# PicoZed.net
KiCad netlist of a schematic drawn in Altium Designer
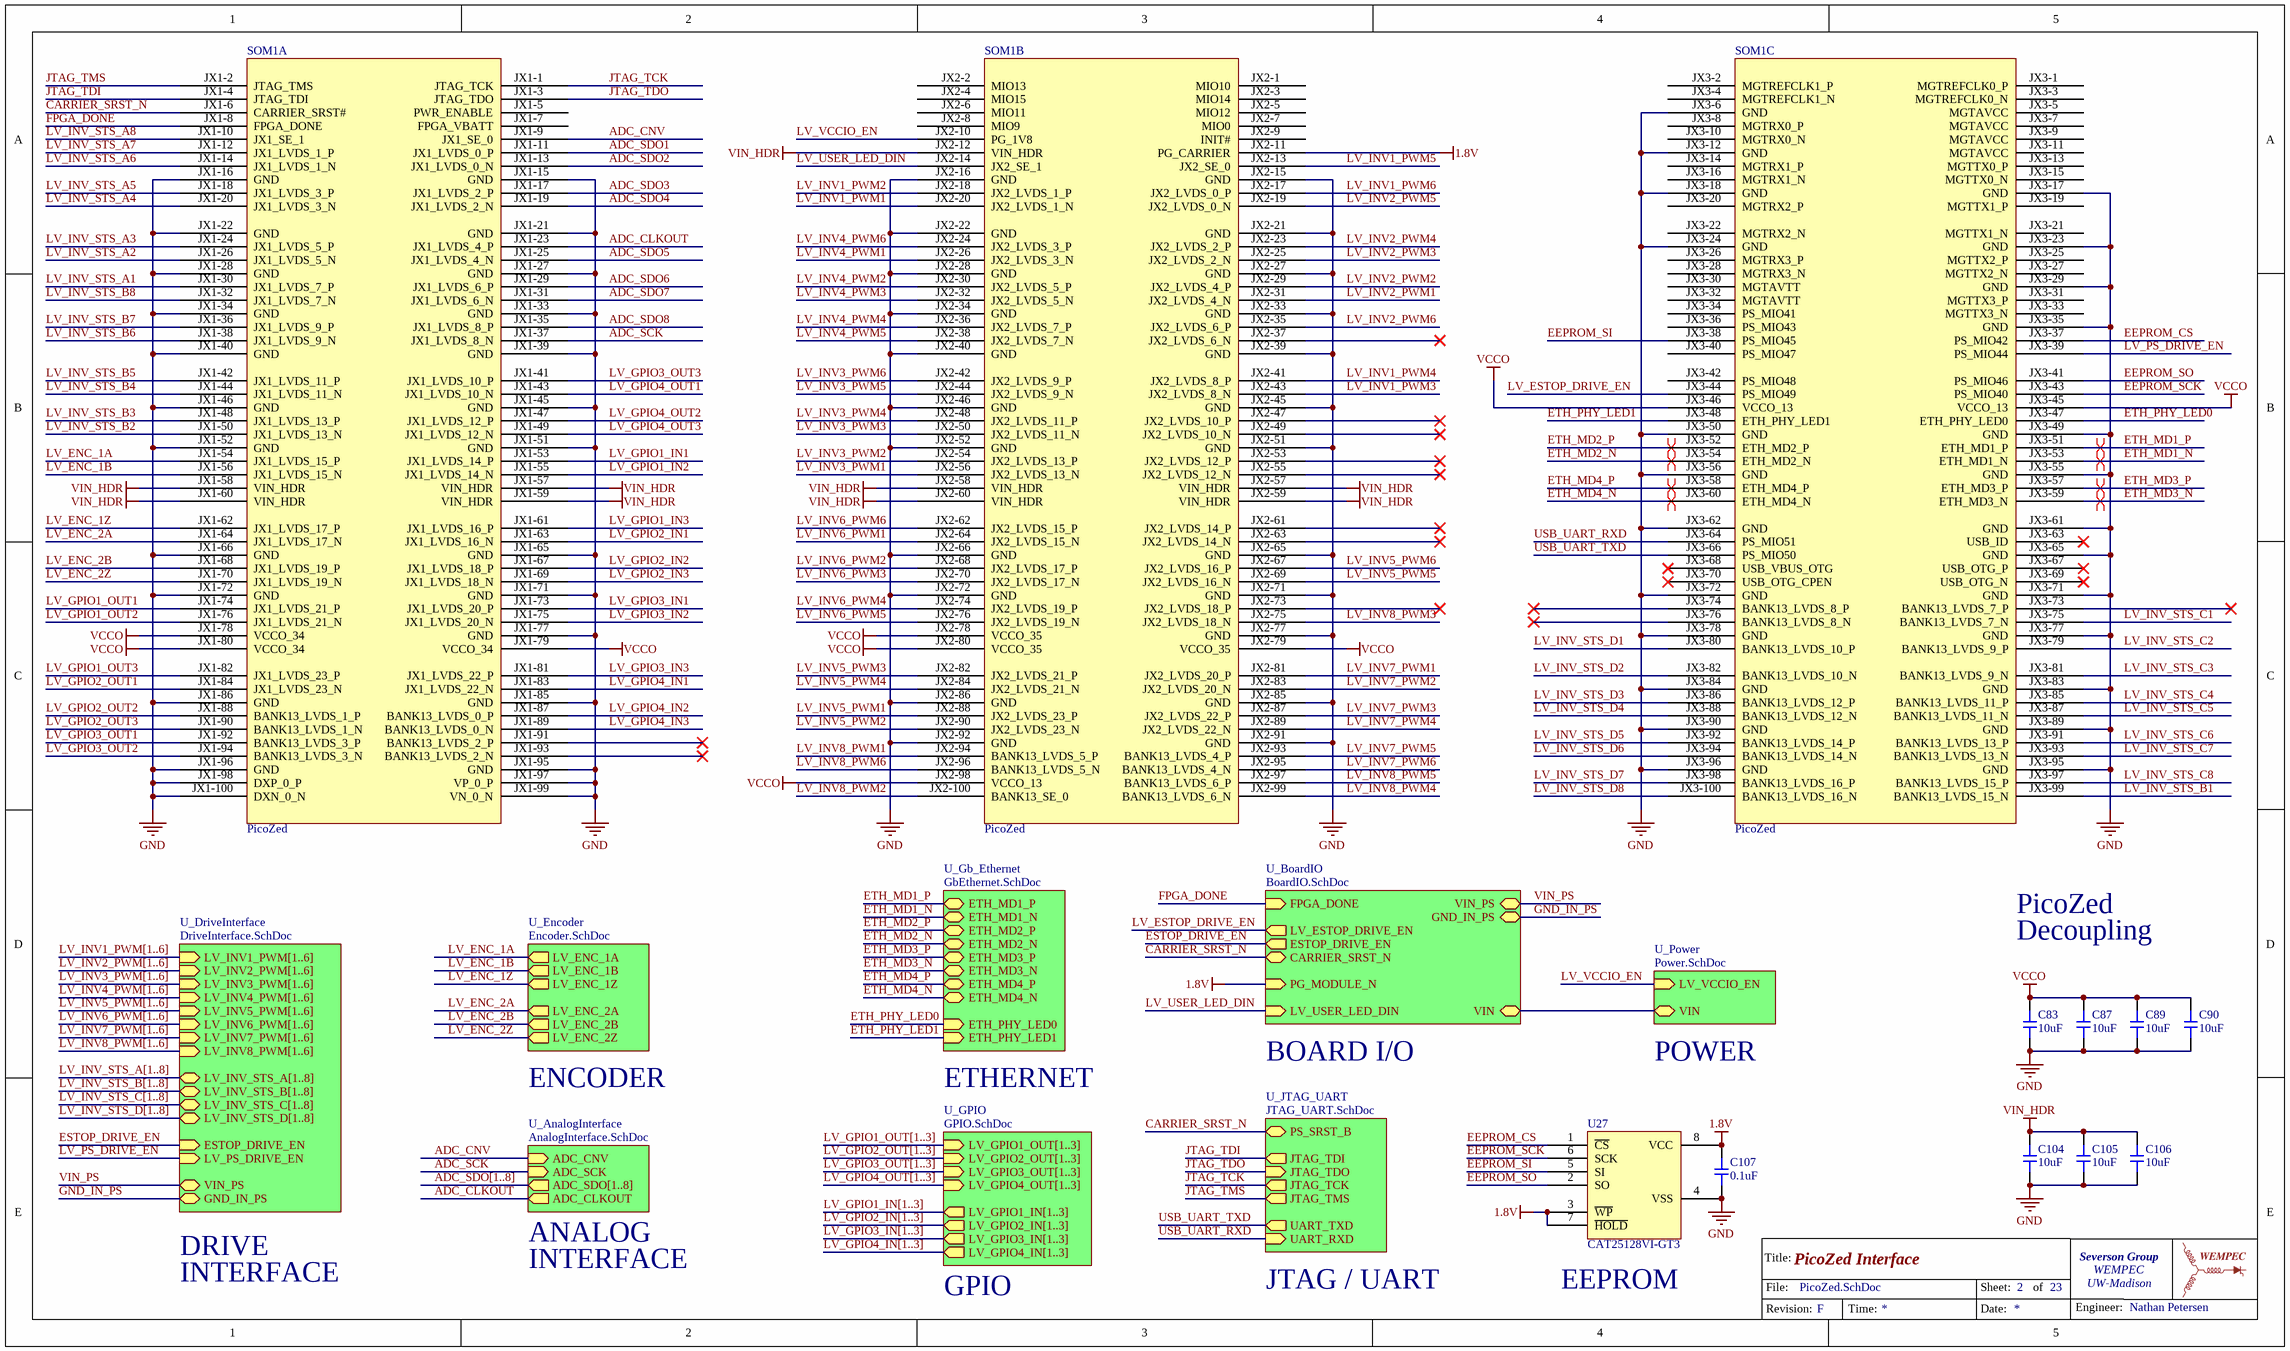
[diagram p0: PicoZed.SchDoc]

(export (version "E")
  (design (tool "Eeschema 10.0.6"))
  (components
    (comp (ref "*") (value "TitleBlockWEMPEC") (libsource (lib "AMDC") (part "TitleBlockWEMPEC")))
    (comp (ref "C83")
      (value "10uF")
      (footprint "0603-CAP")
      (description "Capacitor")
      (libsource (lib "AMDC") (part "Capacitor"))
    )
    (comp (ref "C87")
      (value "10uF")
      (footprint "0603-CAP")
      (description "Capacitor")
      (libsource (lib "AMDC") (part "Capacitor"))
    )
    (comp (ref "C89")
      (value "10uF")
      (footprint "0603-CAP")
      (description "Capacitor")
      (libsource (lib "AMDC") (part "Capacitor"))
    )
    (comp (ref "C90")
      (value "10uF")
      (footprint "0603-CAP")
      (description "Capacitor")
      (libsource (lib "AMDC") (part "Capacitor"))
    )
    (comp (ref "C104")
      (value "10uF")
      (footprint "0603-CAP")
      (description "Capacitor")
      (libsource (lib "AMDC") (part "Capacitor"))
    )
    (comp (ref "C105")
      (value "10uF")
      (footprint "0603-CAP")
      (description "Capacitor")
      (libsource (lib "AMDC") (part "Capacitor"))
    )
    (comp (ref "C106")
      (value "10uF")
      (footprint "0603-CAP")
      (description "Capacitor")
      (libsource (lib "AMDC") (part "Capacitor"))
    )
    (comp (ref "C107")
      (value "0.1uF")
      (footprint "0603-CAP")
      (description "Capacitor")
      (libsource (lib "AMDC") (part "Capacitor"))
    )
    (comp (ref "SOM1")
      (value "PicoZed")
      (footprint "PicoZedSOM")
      (description "PicoZed SOM Carrier Footprint")
      (libsource (lib "PicoZedSchLib") (part "PicoZed_SOM"))
    )
    (comp (ref "U27")
      (value "CAT25128VI-GT3")
      (footprint "SOIC127P600X175-8N")
      (description "IC EEPROM 128K SPI 20MHZ 8SOIC")
      (libsource (lib "AMDC") (part "CAT25128VI-GT3"))
    )
  )
  (nets
    (net (code "1") (name "/ADC_CLKOUT") (class "Default")
      (node (ref "SOM1") (pin "JX1-23") (pinfunction "JX1_LVDS_4_P_JX1-23") (pintype "passive"))
    )
    (net (code "2") (name "/ADC_CNV") (class "Default")
      (node (ref "SOM1") (pin "JX1-9") (pinfunction "JX1_SE_0_JX1-9") (pintype "passive"))
    )
    (net (code "3") (name "/ADC_SCK") (class "Default")
      (node (ref "SOM1") (pin "JX1-37") (pinfunction "JX1_LVDS_8_N_JX1-37") (pintype "passive"))
    )
    (net (code "4") (name "/ADC_SDO1") (class "Default")
      (node (ref "SOM1") (pin "JX1-11") (pinfunction "JX1_LVDS_0_P_JX1-11") (pintype "passive"))
    )
    (net (code "5") (name "/ADC_SDO2") (class "Default")
      (node (ref "SOM1") (pin "JX1-13") (pinfunction "JX1_LVDS_0_N_JX1-13") (pintype "passive"))
    )
    (net (code "6") (name "/ADC_SDO3") (class "Default")
      (node (ref "SOM1") (pin "JX1-17") (pinfunction "JX1_LVDS_2_P_JX1-17") (pintype "passive"))
    )
    (net (code "7") (name "/ADC_SDO4") (class "Default")
      (node (ref "SOM1") (pin "JX1-19") (pinfunction "JX1_LVDS_2_N_JX1-19") (pintype "passive"))
    )
    (net (code "8") (name "/ADC_SDO5") (class "Default")
      (node (ref "SOM1") (pin "JX1-25") (pinfunction "JX1_LVDS_4_N_JX1-25") (pintype "passive"))
    )
    (net (code "9") (name "/ADC_SDO6") (class "Default")
      (node (ref "SOM1") (pin "JX1-29") (pinfunction "JX1_LVDS_6_P_JX1-29") (pintype "passive"))
    )
    (net (code "10") (name "/ADC_SDO7") (class "Default")
      (node (ref "SOM1") (pin "JX1-31") (pinfunction "JX1_LVDS_6_N_JX1-31") (pintype "passive"))
    )
    (net (code "11") (name "/ADC_SDO8") (class "Default")
      (node (ref "SOM1") (pin "JX1-35") (pinfunction "JX1_LVDS_8_P_JX1-35") (pintype "passive"))
    )
    (net (code "13") (name "/CARRIER_SRST_N") (class "Default")
      (node (ref "SOM1") (pin "JX1-6") (pinfunction "CARRIER_SRST#_JX1-6") (pintype "passive"))
    )
    (net (code "14") (name "/EEPROM_CS") (class "Default")
      (node (ref "SOM1") (pin "JX3-37") (pinfunction "PS_MIO42_JX3-37") (pintype "passive"))
      (node (ref "U27") (pin "1") (pinfunction "~{CS}_1") (pintype "passive"))
    )
    (net (code "15") (name "/EEPROM_SCK") (class "Default")
      (node (ref "SOM1") (pin "JX3-43") (pinfunction "PS_MIO40_JX3-43") (pintype "passive"))
      (node (ref "U27") (pin "6") (pinfunction "SCK_6") (pintype "passive"))
    )
    (net (code "16") (name "/EEPROM_SI") (class "Default")
      (node (ref "SOM1") (pin "JX3-38") (pinfunction "PS_MIO45_JX3-38") (pintype "passive"))
      (node (ref "U27") (pin "5") (pinfunction "SI_5") (pintype "passive"))
    )
    (net (code "17") (name "/EEPROM_SO") (class "Default")
      (node (ref "SOM1") (pin "JX3-41") (pinfunction "PS_MIO46_JX3-41") (pintype "passive"))
      (node (ref "U27") (pin "2") (pinfunction "SO_2") (pintype "passive"))
    )
    (net (code "19") (name "/ETH_MD1_N") (class "Default")
      (node (ref "SOM1") (pin "JX3-53") (pinfunction "ETH_MD1_N_JX3-53") (pintype "passive"))
    )
    (net (code "20") (name "/ETH_MD1_P") (class "Default")
      (node (ref "SOM1") (pin "JX3-51") (pinfunction "ETH_MD1_P_JX3-51") (pintype "passive"))
    )
    (net (code "21") (name "/ETH_MD2_N") (class "Default")
      (node (ref "SOM1") (pin "JX3-54") (pinfunction "ETH_MD2_N_JX3-54") (pintype "passive"))
    )
    (net (code "22") (name "/ETH_MD2_P") (class "Default")
      (node (ref "SOM1") (pin "JX3-52") (pinfunction "ETH_MD2_P_JX3-52") (pintype "passive"))
    )
    (net (code "23") (name "/ETH_MD3_N") (class "Default")
      (node (ref "SOM1") (pin "JX3-59") (pinfunction "ETH_MD3_N_JX3-59") (pintype "passive"))
    )
    (net (code "24") (name "/ETH_MD3_P") (class "Default")
      (node (ref "SOM1") (pin "JX3-57") (pinfunction "ETH_MD3_P_JX3-57") (pintype "passive"))
    )
    (net (code "25") (name "/ETH_MD4_N") (class "Default")
      (node (ref "SOM1") (pin "JX3-60") (pinfunction "ETH_MD4_N_JX3-60") (pintype "passive"))
    )
    (net (code "26") (name "/ETH_MD4_P") (class "Default")
      (node (ref "SOM1") (pin "JX3-58") (pinfunction "ETH_MD4_P_JX3-58") (pintype "passive"))
    )
    (net (code "27") (name "/ETH_PHY_LED0") (class "Default")
      (node (ref "SOM1") (pin "JX3-47") (pinfunction "ETH_PHY_LED0_JX3-47") (pintype "passive"))
    )
    (net (code "28") (name "/ETH_PHY_LED1") (class "Default")
      (node (ref "SOM1") (pin "JX3-48") (pinfunction "ETH_PHY_LED1_JX3-48") (pintype "passive"))
    )
    (net (code "29") (name "/FPGA_DONE") (class "Default")
      (node (ref "SOM1") (pin "JX1-8") (pinfunction "FPGA_DONE_JX1-8") (pintype "passive"))
    )
    (net (code "31") (name "/JTAG_TCK") (class "Default")
      (node (ref "SOM1") (pin "JX1-1") (pinfunction "JTAG_TCK_JX1-1") (pintype "passive"))
    )
    (net (code "32") (name "/JTAG_TDI") (class "Default")
      (node (ref "SOM1") (pin "JX1-4") (pinfunction "JTAG_TDI_JX1-4") (pintype "passive"))
    )
    (net (code "33") (name "/JTAG_TDO") (class "Default")
      (node (ref "SOM1") (pin "JX1-3") (pinfunction "JTAG_TDO_JX1-3") (pintype "passive"))
    )
    (net (code "34") (name "/JTAG_TMS") (class "Default")
      (node (ref "SOM1") (pin "JX1-2") (pinfunction "JTAG_TMS_JX1-2") (pintype "passive"))
    )
    (net (code "35") (name "/LV_ENC_1A") (class "Default")
      (node (ref "SOM1") (pin "JX1-54") (pinfunction "JX1_LVDS_15_P_JX1-54") (pintype "passive"))
    )
    (net (code "36") (name "/LV_ENC_1B") (class "Default")
      (node (ref "SOM1") (pin "JX1-56") (pinfunction "JX1_LVDS_15_N_JX1-56") (pintype "passive"))
    )
    (net (code "37") (name "/LV_ENC_1Z") (class "Default")
      (node (ref "SOM1") (pin "JX1-62") (pinfunction "JX1_LVDS_17_P_JX1-62") (pintype "passive"))
    )
    (net (code "38") (name "/LV_ENC_2A") (class "Default")
      (node (ref "SOM1") (pin "JX1-64") (pinfunction "JX1_LVDS_17_N_JX1-64") (pintype "passive"))
    )
    (net (code "39") (name "/LV_ENC_2B") (class "Default")
      (node (ref "SOM1") (pin "JX1-68") (pinfunction "JX1_LVDS_19_P_JX1-68") (pintype "passive"))
    )
    (net (code "40") (name "/LV_ENC_2Z") (class "Default")
      (node (ref "SOM1") (pin "JX1-70") (pinfunction "JX1_LVDS_19_N_JX1-70") (pintype "passive"))
    )
    (net (code "41") (name "/LV_ESTOP_DRIVE_EN") (class "Default")
      (node (ref "SOM1") (pin "JX3-44") (pinfunction "PS_MIO49_JX3-44") (pintype "passive"))
    )
    (net (code "42") (name "/LV_GPIO1_IN1") (class "Default")
      (node (ref "SOM1") (pin "JX1-53") (pinfunction "JX1_LVDS_14_P_JX1-53") (pintype "passive"))
    )
    (net (code "43") (name "/LV_GPIO1_IN2") (class "Default")
      (node (ref "SOM1") (pin "JX1-55") (pinfunction "JX1_LVDS_14_N_JX1-55") (pintype "passive"))
    )
    (net (code "44") (name "/LV_GPIO1_IN3") (class "Default")
      (node (ref "SOM1") (pin "JX1-61") (pinfunction "JX1_LVDS_16_P_JX1-61") (pintype "passive"))
    )
    (net (code "46") (name "/LV_GPIO1_OUT1") (class "Default")
      (node (ref "SOM1") (pin "JX1-74") (pinfunction "JX1_LVDS_21_P_JX1-74") (pintype "passive"))
    )
    (net (code "47") (name "/LV_GPIO1_OUT2") (class "Default")
      (node (ref "SOM1") (pin "JX1-76") (pinfunction "JX1_LVDS_21_N_JX1-76") (pintype "passive"))
    )
    (net (code "48") (name "/LV_GPIO1_OUT3") (class "Default")
      (node (ref "SOM1") (pin "JX1-82") (pinfunction "JX1_LVDS_23_P_JX1-82") (pintype "passive"))
    )
    (net (code "50") (name "/LV_GPIO2_IN1") (class "Default")
      (node (ref "SOM1") (pin "JX1-63") (pinfunction "JX1_LVDS_16_N_JX1-63") (pintype "passive"))
    )
    (net (code "51") (name "/LV_GPIO2_IN2") (class "Default")
      (node (ref "SOM1") (pin "JX1-67") (pinfunction "JX1_LVDS_18_P_JX1-67") (pintype "passive"))
    )
    (net (code "52") (name "/LV_GPIO2_IN3") (class "Default")
      (node (ref "SOM1") (pin "JX1-69") (pinfunction "JX1_LVDS_18_N_JX1-69") (pintype "passive"))
    )
    (net (code "54") (name "/LV_GPIO2_OUT1") (class "Default")
      (node (ref "SOM1") (pin "JX1-84") (pinfunction "JX1_LVDS_23_N_JX1-84") (pintype "passive"))
    )
    (net (code "55") (name "/LV_GPIO2_OUT2") (class "Default")
      (node (ref "SOM1") (pin "JX1-88") (pinfunction "BANK13_LVDS_1_P_JX1-88") (pintype "passive"))
    )
    (net (code "56") (name "/LV_GPIO2_OUT3") (class "Default")
      (node (ref "SOM1") (pin "JX1-90") (pinfunction "BANK13_LVDS_1_N_JX1-90") (pintype "passive"))
    )
    (net (code "58") (name "/LV_GPIO3_IN1") (class "Default")
      (node (ref "SOM1") (pin "JX1-73") (pinfunction "JX1_LVDS_20_P_JX1-73") (pintype "passive"))
    )
    (net (code "59") (name "/LV_GPIO3_IN2") (class "Default")
      (node (ref "SOM1") (pin "JX1-75") (pinfunction "JX1_LVDS_20_N_JX1-75") (pintype "passive"))
    )
    (net (code "60") (name "/LV_GPIO3_IN3") (class "Default")
      (node (ref "SOM1") (pin "JX1-81") (pinfunction "JX1_LVDS_22_P_JX1-81") (pintype "passive"))
    )
    (net (code "62") (name "/LV_GPIO3_OUT1") (class "Default")
      (node (ref "SOM1") (pin "JX1-92") (pinfunction "BANK13_LVDS_3_P_JX1-92") (pintype "passive"))
    )
    (net (code "63") (name "/LV_GPIO3_OUT2") (class "Default")
      (node (ref "SOM1") (pin "JX1-94") (pinfunction "BANK13_LVDS_3_N_JX1-94") (pintype "passive"))
    )
    (net (code "64") (name "/LV_GPIO3_OUT3") (class "Default")
      (node (ref "SOM1") (pin "JX1-41") (pinfunction "JX1_LVDS_10_P_JX1-41") (pintype "passive"))
    )
    (net (code "66") (name "/LV_GPIO4_IN1") (class "Default")
      (node (ref "SOM1") (pin "JX1-83") (pinfunction "JX1_LVDS_22_N_JX1-83") (pintype "passive"))
    )
    (net (code "67") (name "/LV_GPIO4_IN2") (class "Default")
      (node (ref "SOM1") (pin "JX1-87") (pinfunction "BANK13_LVDS_0_P_JX1-87") (pintype "passive"))
    )
    (net (code "68") (name "/LV_GPIO4_IN3") (class "Default")
      (node (ref "SOM1") (pin "JX1-89") (pinfunction "BANK13_LVDS_0_N_JX1-89") (pintype "passive"))
    )
    (net (code "70") (name "/LV_GPIO4_OUT1") (class "Default")
      (node (ref "SOM1") (pin "JX1-43") (pinfunction "JX1_LVDS_10_N_JX1-43") (pintype "passive"))
    )
    (net (code "71") (name "/LV_GPIO4_OUT2") (class "Default")
      (node (ref "SOM1") (pin "JX1-47") (pinfunction "JX1_LVDS_12_P_JX1-47") (pintype "passive"))
    )
    (net (code "72") (name "/LV_GPIO4_OUT3") (class "Default")
      (node (ref "SOM1") (pin "JX1-49") (pinfunction "JX1_LVDS_12_N_JX1-49") (pintype "passive"))
    )
    (net (code "74") (name "/LV_INV1_PWM1") (class "Default")
      (node (ref "SOM1") (pin "JX2-20") (pinfunction "JX2_LVDS_1_N_JX2-20") (pintype "passive"))
    )
    (net (code "75") (name "/LV_INV1_PWM2") (class "Default")
      (node (ref "SOM1") (pin "JX2-18") (pinfunction "JX2_LVDS_1_P_JX2-18") (pintype "passive"))
    )
    (net (code "76") (name "/LV_INV1_PWM3") (class "Default")
      (node (ref "SOM1") (pin "JX2-43") (pinfunction "JX2_LVDS_8_N_JX2-43") (pintype "passive"))
    )
    (net (code "77") (name "/LV_INV1_PWM4") (class "Default")
      (node (ref "SOM1") (pin "JX2-41") (pinfunction "JX2_LVDS_8_P_JX2-41") (pintype "passive"))
    )
    (net (code "78") (name "/LV_INV1_PWM5") (class "Default")
      (node (ref "SOM1") (pin "JX2-13") (pinfunction "JX2_SE_0_JX2-13") (pintype "passive"))
    )
    (net (code "79") (name "/LV_INV1_PWM6") (class "Default")
      (node (ref "SOM1") (pin "JX2-17") (pinfunction "JX2_LVDS_0_P_JX2-17") (pintype "passive"))
    )
    (net (code "81") (name "/LV_INV2_PWM1") (class "Default")
      (node (ref "SOM1") (pin "JX2-31") (pinfunction "JX2_LVDS_4_N_JX2-31") (pintype "passive"))
    )
    (net (code "82") (name "/LV_INV2_PWM2") (class "Default")
      (node (ref "SOM1") (pin "JX2-29") (pinfunction "JX2_LVDS_4_P_JX2-29") (pintype "passive"))
    )
    (net (code "83") (name "/LV_INV2_PWM3") (class "Default")
      (node (ref "SOM1") (pin "JX2-25") (pinfunction "JX2_LVDS_2_N_JX2-25") (pintype "passive"))
    )
    (net (code "84") (name "/LV_INV2_PWM4") (class "Default")
      (node (ref "SOM1") (pin "JX2-23") (pinfunction "JX2_LVDS_2_P_JX2-23") (pintype "passive"))
    )
    (net (code "85") (name "/LV_INV2_PWM5") (class "Default")
      (node (ref "SOM1") (pin "JX2-19") (pinfunction "JX2_LVDS_0_N_JX2-19") (pintype "passive"))
    )
    (net (code "86") (name "/LV_INV2_PWM6") (class "Default")
      (node (ref "SOM1") (pin "JX2-35") (pinfunction "JX2_LVDS_6_P_JX2-35") (pintype "passive"))
    )
    (net (code "88") (name "/LV_INV3_PWM1") (class "Default")
      (node (ref "SOM1") (pin "JX2-56") (pinfunction "JX2_LVDS_13_N_JX2-56") (pintype "passive"))
    )
    (net (code "89") (name "/LV_INV3_PWM2") (class "Default")
      (node (ref "SOM1") (pin "JX2-54") (pinfunction "JX2_LVDS_13_P_JX2-54") (pintype "passive"))
    )
    (net (code "90") (name "/LV_INV3_PWM3") (class "Default")
      (node (ref "SOM1") (pin "JX2-50") (pinfunction "JX2_LVDS_11_N_JX2-50") (pintype "passive"))
    )
    (net (code "91") (name "/LV_INV3_PWM4") (class "Default")
      (node (ref "SOM1") (pin "JX2-48") (pinfunction "JX2_LVDS_11_P_JX2-48") (pintype "passive"))
    )
    (net (code "92") (name "/LV_INV3_PWM5") (class "Default")
      (node (ref "SOM1") (pin "JX2-44") (pinfunction "JX2_LVDS_9_N_JX2-44") (pintype "passive"))
    )
    (net (code "93") (name "/LV_INV3_PWM6") (class "Default")
      (node (ref "SOM1") (pin "JX2-42") (pinfunction "JX2_LVDS_9_P_JX2-42") (pintype "passive"))
    )
    (net (code "95") (name "/LV_INV4_PWM1") (class "Default")
      (node (ref "SOM1") (pin "JX2-26") (pinfunction "JX2_LVDS_3_N_JX2-26") (pintype "passive"))
    )
    (net (code "96") (name "/LV_INV4_PWM2") (class "Default")
      (node (ref "SOM1") (pin "JX2-30") (pinfunction "JX2_LVDS_5_P_JX2-30") (pintype "passive"))
    )
    (net (code "97") (name "/LV_INV4_PWM3") (class "Default")
      (node (ref "SOM1") (pin "JX2-32") (pinfunction "JX2_LVDS_5_N_JX2-32") (pintype "passive"))
    )
    (net (code "98") (name "/LV_INV4_PWM4") (class "Default")
      (node (ref "SOM1") (pin "JX2-36") (pinfunction "JX2_LVDS_7_P_JX2-36") (pintype "passive"))
    )
    (net (code "99") (name "/LV_INV4_PWM5") (class "Default")
      (node (ref "SOM1") (pin "JX2-38") (pinfunction "JX2_LVDS_7_N_JX2-38") (pintype "passive"))
    )
    (net (code "100") (name "/LV_INV4_PWM6") (class "Default")
      (node (ref "SOM1") (pin "JX2-24") (pinfunction "JX2_LVDS_3_P_JX2-24") (pintype "passive"))
    )
    (net (code "102") (name "/LV_INV5_PWM1") (class "Default")
      (node (ref "SOM1") (pin "JX2-88") (pinfunction "JX2_LVDS_23_P_JX2-88") (pintype "passive"))
    )
    (net (code "103") (name "/LV_INV5_PWM2") (class "Default")
      (node (ref "SOM1") (pin "JX2-90") (pinfunction "JX2_LVDS_23_N_JX2-90") (pintype "passive"))
    )
    (net (code "104") (name "/LV_INV5_PWM3") (class "Default")
      (node (ref "SOM1") (pin "JX2-82") (pinfunction "JX2_LVDS_21_P_JX2-82") (pintype "passive"))
    )
    (net (code "105") (name "/LV_INV5_PWM4") (class "Default")
      (node (ref "SOM1") (pin "JX2-84") (pinfunction "JX2_LVDS_21_N_JX2-84") (pintype "passive"))
    )
    (net (code "106") (name "/LV_INV5_PWM5") (class "Default")
      (node (ref "SOM1") (pin "JX2-69") (pinfunction "JX2_LVDS_16_N_JX2-69") (pintype "passive"))
    )
    (net (code "107") (name "/LV_INV5_PWM6") (class "Default")
      (node (ref "SOM1") (pin "JX2-67") (pinfunction "JX2_LVDS_16_P_JX2-67") (pintype "passive"))
    )
    (net (code "109") (name "/LV_INV6_PWM1") (class "Default")
      (node (ref "SOM1") (pin "JX2-64") (pinfunction "JX2_LVDS_15_N_JX2-64") (pintype "passive"))
    )
    (net (code "110") (name "/LV_INV6_PWM2") (class "Default")
      (node (ref "SOM1") (pin "JX2-68") (pinfunction "JX2_LVDS_17_P_JX2-68") (pintype "passive"))
    )
    (net (code "111") (name "/LV_INV6_PWM3") (class "Default")
      (node (ref "SOM1") (pin "JX2-70") (pinfunction "JX2_LVDS_17_N_JX2-70") (pintype "passive"))
    )
    (net (code "112") (name "/LV_INV6_PWM4") (class "Default")
      (node (ref "SOM1") (pin "JX2-74") (pinfunction "JX2_LVDS_19_P_JX2-74") (pintype "passive"))
    )
    (net (code "113") (name "/LV_INV6_PWM5") (class "Default")
      (node (ref "SOM1") (pin "JX2-76") (pinfunction "JX2_LVDS_19_N_JX2-76") (pintype "passive"))
    )
    (net (code "114") (name "/LV_INV6_PWM6") (class "Default")
      (node (ref "SOM1") (pin "JX2-62") (pinfunction "JX2_LVDS_15_P_JX2-62") (pintype "passive"))
    )
    (net (code "116") (name "/LV_INV7_PWM1") (class "Default")
      (node (ref "SOM1") (pin "JX2-81") (pinfunction "JX2_LVDS_20_P_JX2-81") (pintype "passive"))
    )
    (net (code "117") (name "/LV_INV7_PWM2") (class "Default")
      (node (ref "SOM1") (pin "JX2-83") (pinfunction "JX2_LVDS_20_N_JX2-83") (pintype "passive"))
    )
    (net (code "118") (name "/LV_INV7_PWM3") (class "Default")
      (node (ref "SOM1") (pin "JX2-87") (pinfunction "JX2_LVDS_22_P_JX2-87") (pintype "passive"))
    )
    (net (code "119") (name "/LV_INV7_PWM4") (class "Default")
      (node (ref "SOM1") (pin "JX2-89") (pinfunction "JX2_LVDS_22_N_JX2-89") (pintype "passive"))
    )
    (net (code "120") (name "/LV_INV7_PWM5") (class "Default")
      (node (ref "SOM1") (pin "JX2-93") (pinfunction "BANK13_LVDS_4_P_JX2-93") (pintype "passive"))
    )
    (net (code "121") (name "/LV_INV7_PWM6") (class "Default")
      (node (ref "SOM1") (pin "JX2-95") (pinfunction "BANK13_LVDS_4_N_JX2-95") (pintype "passive"))
    )
    (net (code "123") (name "/LV_INV8_PWM1") (class "Default")
      (node (ref "SOM1") (pin "JX2-94") (pinfunction "BANK13_LVDS_5_P_JX2-94") (pintype "passive"))
    )
    (net (code "124") (name "/LV_INV8_PWM2") (class "Default")
      (node (ref "SOM1") (pin "JX2-100") (pinfunction "BANK13_SE_0_JX2-100") (pintype "passive"))
    )
    (net (code "125") (name "/LV_INV8_PWM3") (class "Default")
      (node (ref "SOM1") (pin "JX2-75") (pinfunction "JX2_LVDS_18_N_JX2-75") (pintype "passive"))
    )
    (net (code "126") (name "/LV_INV8_PWM4") (class "Default")
      (node (ref "SOM1") (pin "JX2-99") (pinfunction "BANK13_LVDS_6_N_JX2-99") (pintype "passive"))
    )
    (net (code "127") (name "/LV_INV8_PWM5") (class "Default")
      (node (ref "SOM1") (pin "JX2-97") (pinfunction "BANK13_LVDS_6_P_JX2-97") (pintype "passive"))
    )
    (net (code "128") (name "/LV_INV8_PWM6") (class "Default")
      (node (ref "SOM1") (pin "JX2-96") (pinfunction "BANK13_LVDS_5_N_JX2-96") (pintype "passive"))
    )
    (net (code "130") (name "/LV_INV_STS_A1") (class "Default")
      (node (ref "SOM1") (pin "JX1-30") (pinfunction "JX1_LVDS_7_P_JX1-30") (pintype "passive"))
    )
    (net (code "131") (name "/LV_INV_STS_A2") (class "Default")
      (node (ref "SOM1") (pin "JX1-26") (pinfunction "JX1_LVDS_5_N_JX1-26") (pintype "passive"))
    )
    (net (code "132") (name "/LV_INV_STS_A3") (class "Default")
      (node (ref "SOM1") (pin "JX1-24") (pinfunction "JX1_LVDS_5_P_JX1-24") (pintype "passive"))
    )
    (net (code "133") (name "/LV_INV_STS_A4") (class "Default")
      (node (ref "SOM1") (pin "JX1-20") (pinfunction "JX1_LVDS_3_N_JX1-20") (pintype "passive"))
    )
    (net (code "134") (name "/LV_INV_STS_A5") (class "Default")
      (node (ref "SOM1") (pin "JX1-18") (pinfunction "JX1_LVDS_3_P_JX1-18") (pintype "passive"))
    )
    (net (code "135") (name "/LV_INV_STS_A6") (class "Default")
      (node (ref "SOM1") (pin "JX1-14") (pinfunction "JX1_LVDS_1_N_JX1-14") (pintype "passive"))
    )
    (net (code "136") (name "/LV_INV_STS_A7") (class "Default")
      (node (ref "SOM1") (pin "JX1-12") (pinfunction "JX1_LVDS_1_P_JX1-12") (pintype "passive"))
    )
    (net (code "137") (name "/LV_INV_STS_A8") (class "Default")
      (node (ref "SOM1") (pin "JX1-10") (pinfunction "JX1_SE_1_JX1-10") (pintype "passive"))
    )
    (net (code "139") (name "/LV_INV_STS_B1") (class "Default")
      (node (ref "SOM1") (pin "JX3-99") (pinfunction "BANK13_LVDS_15_N_JX3-99") (pintype "passive"))
    )
    (net (code "140") (name "/LV_INV_STS_B2") (class "Default")
      (node (ref "SOM1") (pin "JX1-50") (pinfunction "JX1_LVDS_13_N_JX1-50") (pintype "passive"))
    )
    (net (code "141") (name "/LV_INV_STS_B3") (class "Default")
      (node (ref "SOM1") (pin "JX1-48") (pinfunction "JX1_LVDS_13_P_JX1-48") (pintype "passive"))
    )
    (net (code "142") (name "/LV_INV_STS_B4") (class "Default")
      (node (ref "SOM1") (pin "JX1-44") (pinfunction "JX1_LVDS_11_N_JX1-44") (pintype "passive"))
    )
    (net (code "143") (name "/LV_INV_STS_B5") (class "Default")
      (node (ref "SOM1") (pin "JX1-42") (pinfunction "JX1_LVDS_11_P_JX1-42") (pintype "passive"))
    )
    (net (code "144") (name "/LV_INV_STS_B6") (class "Default")
      (node (ref "SOM1") (pin "JX1-38") (pinfunction "JX1_LVDS_9_N_JX1-38") (pintype "passive"))
    )
    (net (code "145") (name "/LV_INV_STS_B7") (class "Default")
      (node (ref "SOM1") (pin "JX1-36") (pinfunction "JX1_LVDS_9_P_JX1-36") (pintype "passive"))
    )
    (net (code "146") (name "/LV_INV_STS_B8") (class "Default")
      (node (ref "SOM1") (pin "JX1-32") (pinfunction "JX1_LVDS_7_N_JX1-32") (pintype "passive"))
    )
    (net (code "148") (name "/LV_INV_STS_C1") (class "Default")
      (node (ref "SOM1") (pin "JX3-75") (pinfunction "BANK13_LVDS_7_N_JX3-75") (pintype "passive"))
    )
    (net (code "149") (name "/LV_INV_STS_C2") (class "Default")
      (node (ref "SOM1") (pin "JX3-79") (pinfunction "BANK13_LVDS_9_P_JX3-79") (pintype "passive"))
    )
    (net (code "150") (name "/LV_INV_STS_C3") (class "Default")
      (node (ref "SOM1") (pin "JX3-81") (pinfunction "BANK13_LVDS_9_N_JX3-81") (pintype "passive"))
    )
    (net (code "151") (name "/LV_INV_STS_C4") (class "Default")
      (node (ref "SOM1") (pin "JX3-85") (pinfunction "BANK13_LVDS_11_P_JX3-85") (pintype "passive"))
    )
    (net (code "152") (name "/LV_INV_STS_C5") (class "Default")
      (node (ref "SOM1") (pin "JX3-87") (pinfunction "BANK13_LVDS_11_N_JX3-87") (pintype "passive"))
    )
    (net (code "153") (name "/LV_INV_STS_C6") (class "Default")
      (node (ref "SOM1") (pin "JX3-91") (pinfunction "BANK13_LVDS_13_P_JX3-91") (pintype "passive"))
    )
    (net (code "154") (name "/LV_INV_STS_C7") (class "Default")
      (node (ref "SOM1") (pin "JX3-93") (pinfunction "BANK13_LVDS_13_N_JX3-93") (pintype "passive"))
    )
    (net (code "155") (name "/LV_INV_STS_C8") (class "Default")
      (node (ref "SOM1") (pin "JX3-97") (pinfunction "BANK13_LVDS_15_P_JX3-97") (pintype "passive"))
    )
    (net (code "157") (name "/LV_INV_STS_D1") (class "Default")
      (node (ref "SOM1") (pin "JX3-80") (pinfunction "BANK13_LVDS_10_P_JX3-80") (pintype "passive"))
    )
    (net (code "158") (name "/LV_INV_STS_D2") (class "Default")
      (node (ref "SOM1") (pin "JX3-82") (pinfunction "BANK13_LVDS_10_N_JX3-82") (pintype "passive"))
    )
    (net (code "159") (name "/LV_INV_STS_D3") (class "Default")
      (node (ref "SOM1") (pin "JX3-86") (pinfunction "BANK13_LVDS_12_P_JX3-86") (pintype "passive"))
    )
    (net (code "160") (name "/LV_INV_STS_D4") (class "Default")
      (node (ref "SOM1") (pin "JX3-88") (pinfunction "BANK13_LVDS_12_N_JX3-88") (pintype "passive"))
    )
    (net (code "161") (name "/LV_INV_STS_D5") (class "Default")
      (node (ref "SOM1") (pin "JX3-92") (pinfunction "BANK13_LVDS_14_P_JX3-92") (pintype "passive"))
    )
    (net (code "162") (name "/LV_INV_STS_D6") (class "Default")
      (node (ref "SOM1") (pin "JX3-94") (pinfunction "BANK13_LVDS_14_N_JX3-94") (pintype "passive"))
    )
    (net (code "163") (name "/LV_INV_STS_D7") (class "Default")
      (node (ref "SOM1") (pin "JX3-98") (pinfunction "BANK13_LVDS_16_P_JX3-98") (pintype "passive"))
    )
    (net (code "164") (name "/LV_INV_STS_D8") (class "Default")
      (node (ref "SOM1") (pin "JX3-100") (pinfunction "BANK13_LVDS_16_N_JX3-100") (pintype "passive"))
    )
    (net (code "166") (name "/LV_PS_DRIVE_EN") (class "Default")
      (node (ref "SOM1") (pin "JX3-39") (pinfunction "PS_MIO44_JX3-39") (pintype "passive"))
    )
    (net (code "167") (name "/LV_USER_LED_DIN") (class "Default")
      (node (ref "SOM1") (pin "JX2-14") (pinfunction "JX2_SE_1_JX2-14") (pintype "passive"))
    )
    (net (code "168") (name "/LV_VCCIO_EN") (class "Default")
      (node (ref "SOM1") (pin "JX2-10") (pinfunction "PG_1V8_JX2-10") (pintype "passive"))
    )
    (net (code "169") (name "/USB_UART_RXD") (class "Default")
      (node (ref "SOM1") (pin "JX3-64") (pinfunction "PS_MIO51_JX3-64") (pintype "passive"))
    )
    (net (code "170") (name "/USB_UART_TXD") (class "Default")
      (node (ref "SOM1") (pin "JX3-66") (pinfunction "PS_MIO50_JX3-66") (pintype "passive"))
    )
    (net (code "173") (name "1.8V") (class "Default")
      (node (ref "C107") (pin "2") (pinfunction "2_2") (pintype "passive"))
      (node (ref "SOM1") (pin "JX2-11") (pinfunction "PG_CARRIER_JX2-11") (pintype "passive"))
      (node (ref "U27") (pin "3") (pinfunction "~{WP}_3") (pintype "passive"))
      (node (ref "U27") (pin "7") (pinfunction "~{HOLD}_7") (pintype "passive"))
      (node (ref "U27") (pin "8") (pinfunction "VCC_8") (pintype "passive"))
    )
    (net (code "174") (name "GND") (class "Default")
      (node (ref "C104") (pin "1") (pinfunction "1_1") (pintype "passive"))
      (node (ref "C105") (pin "1") (pinfunction "1_1") (pintype "passive"))
      (node (ref "C106") (pin "1") (pinfunction "1_1") (pintype "passive"))
      (node (ref "C107") (pin "1") (pinfunction "1_1") (pintype "passive"))
      (node (ref "C83") (pin "1") (pinfunction "1_1") (pintype "passive"))
      (node (ref "C87") (pin "1") (pinfunction "1_1") (pintype "passive"))
      (node (ref "C89") (pin "1") (pinfunction "1_1") (pintype "passive"))
      (node (ref "C90") (pin "1") (pinfunction "1_1") (pintype "passive"))
      (node (ref "SOM1") (pin "JX1-100") (pinfunction "DXN_0_N_JX1-100") (pintype "passive"))
      (node (ref "SOM1") (pin "JX1-15") (pinfunction "GND_JX1-15") (pintype "passive"))
      (node (ref "SOM1") (pin "JX1-16") (pinfunction "GND_JX1-16") (pintype "passive"))
      (node (ref "SOM1") (pin "JX1-21") (pinfunction "GND_JX1-21") (pintype "passive"))
      (node (ref "SOM1") (pin "JX1-22") (pinfunction "GND_JX1-22") (pintype "passive"))
      (node (ref "SOM1") (pin "JX1-27") (pinfunction "GND_JX1-27") (pintype "passive"))
      (node (ref "SOM1") (pin "JX1-28") (pinfunction "GND_JX1-28") (pintype "passive"))
      (node (ref "SOM1") (pin "JX1-33") (pinfunction "GND_JX1-33") (pintype "passive"))
      (node (ref "SOM1") (pin "JX1-34") (pinfunction "GND_JX1-34") (pintype "passive"))
      (node (ref "SOM1") (pin "JX1-39") (pinfunction "GND_JX1-39") (pintype "passive"))
      (node (ref "SOM1") (pin "JX1-40") (pinfunction "GND_JX1-40") (pintype "passive"))
      (node (ref "SOM1") (pin "JX1-45") (pinfunction "GND_JX1-45") (pintype "passive"))
      (node (ref "SOM1") (pin "JX1-46") (pinfunction "GND_JX1-46") (pintype "passive"))
      (node (ref "SOM1") (pin "JX1-51") (pinfunction "GND_JX1-51") (pintype "passive"))
      (node (ref "SOM1") (pin "JX1-52") (pinfunction "GND_JX1-52") (pintype "passive"))
      (node (ref "SOM1") (pin "JX1-65") (pinfunction "GND_JX1-65") (pintype "passive"))
      (node (ref "SOM1") (pin "JX1-66") (pinfunction "GND_JX1-66") (pintype "passive"))
      (node (ref "SOM1") (pin "JX1-71") (pinfunction "GND_JX1-71") (pintype "passive"))
      (node (ref "SOM1") (pin "JX1-72") (pinfunction "GND_JX1-72") (pintype "passive"))
      (node (ref "SOM1") (pin "JX1-77") (pinfunction "GND_JX1-77") (pintype "passive"))
      (node (ref "SOM1") (pin "JX1-85") (pinfunction "GND_JX1-85") (pintype "passive"))
      (node (ref "SOM1") (pin "JX1-86") (pinfunction "GND_JX1-86") (pintype "passive"))
      (node (ref "SOM1") (pin "JX1-95") (pinfunction "GND_JX1-95") (pintype "passive"))
      (node (ref "SOM1") (pin "JX1-96") (pinfunction "GND_JX1-96") (pintype "passive"))
      (node (ref "SOM1") (pin "JX1-97") (pinfunction "VP_0_P_JX1-97") (pintype "passive"))
      (node (ref "SOM1") (pin "JX1-98") (pinfunction "DXP_0_P_JX1-98") (pintype "passive"))
      (node (ref "SOM1") (pin "JX1-99") (pinfunction "VN_0_N_JX1-99") (pintype "passive"))
      (node (ref "SOM1") (pin "JX2-15") (pinfunction "GND_JX2-15") (pintype "passive"))
      (node (ref "SOM1") (pin "JX2-16") (pinfunction "GND_JX2-16") (pintype "passive"))
      (node (ref "SOM1") (pin "JX2-21") (pinfunction "GND_JX2-21") (pintype "passive"))
      (node (ref "SOM1") (pin "JX2-22") (pinfunction "GND_JX2-22") (pintype "passive"))
      (node (ref "SOM1") (pin "JX2-27") (pinfunction "GND_JX2-27") (pintype "passive"))
      (node (ref "SOM1") (pin "JX2-28") (pinfunction "GND_JX2-28") (pintype "passive"))
      (node (ref "SOM1") (pin "JX2-33") (pinfunction "GND_JX2-33") (pintype "passive"))
      (node (ref "SOM1") (pin "JX2-34") (pinfunction "GND_JX2-34") (pintype "passive"))
      (node (ref "SOM1") (pin "JX2-39") (pinfunction "GND_JX2-39") (pintype "passive"))
      (node (ref "SOM1") (pin "JX2-40") (pinfunction "GND_JX2-40") (pintype "passive"))
      (node (ref "SOM1") (pin "JX2-45") (pinfunction "GND_JX2-45") (pintype "passive"))
      (node (ref "SOM1") (pin "JX2-46") (pinfunction "GND_JX2-46") (pintype "passive"))
      (node (ref "SOM1") (pin "JX2-51") (pinfunction "GND_JX2-51") (pintype "passive"))
      (node (ref "SOM1") (pin "JX2-52") (pinfunction "GND_JX2-52") (pintype "passive"))
      (node (ref "SOM1") (pin "JX2-65") (pinfunction "GND_JX2-65") (pintype "passive"))
      (node (ref "SOM1") (pin "JX2-66") (pinfunction "GND_JX2-66") (pintype "passive"))
      (node (ref "SOM1") (pin "JX2-71") (pinfunction "GND_JX2-71") (pintype "passive"))
      (node (ref "SOM1") (pin "JX2-72") (pinfunction "GND_JX2-72") (pintype "passive"))
      (node (ref "SOM1") (pin "JX2-77") (pinfunction "GND_JX2-77") (pintype "passive"))
      (node (ref "SOM1") (pin "JX2-85") (pinfunction "GND_JX2-85") (pintype "passive"))
      (node (ref "SOM1") (pin "JX2-86") (pinfunction "GND_JX2-86") (pintype "passive"))
      (node (ref "SOM1") (pin "JX2-91") (pinfunction "GND_JX2-91") (pintype "passive"))
      (node (ref "SOM1") (pin "JX2-92") (pinfunction "GND_JX2-92") (pintype "passive"))
      (node (ref "SOM1") (pin "JX3-12") (pinfunction "GND_JX3-12") (pintype "passive"))
      (node (ref "SOM1") (pin "JX3-17") (pinfunction "GND_JX3-17") (pintype "passive"))
      (node (ref "SOM1") (pin "JX3-18") (pinfunction "GND_JX3-18") (pintype "passive"))
      (node (ref "SOM1") (pin "JX3-23") (pinfunction "GND_JX3-23") (pintype "passive"))
      (node (ref "SOM1") (pin "JX3-24") (pinfunction "GND_JX3-24") (pintype "passive"))
      (node (ref "SOM1") (pin "JX3-29") (pinfunction "GND_JX3-29") (pintype "passive"))
      (node (ref "SOM1") (pin "JX3-35") (pinfunction "GND_JX3-35") (pintype "passive"))
      (node (ref "SOM1") (pin "JX3-49") (pinfunction "GND_JX3-49") (pintype "passive"))
      (node (ref "SOM1") (pin "JX3-50") (pinfunction "GND_JX3-50") (pintype "passive"))
      (node (ref "SOM1") (pin "JX3-55") (pinfunction "GND_JX3-55") (pintype "passive"))
      (node (ref "SOM1") (pin "JX3-56") (pinfunction "GND_JX3-56") (pintype "passive"))
      (node (ref "SOM1") (pin "JX3-6") (pinfunction "GND_JX3-6") (pintype "passive"))
      (node (ref "SOM1") (pin "JX3-61") (pinfunction "GND_JX3-61") (pintype "passive"))
      (node (ref "SOM1") (pin "JX3-62") (pinfunction "GND_JX3-62") (pintype "passive"))
      (node (ref "SOM1") (pin "JX3-65") (pinfunction "GND_JX3-65") (pintype "passive"))
      (node (ref "SOM1") (pin "JX3-71") (pinfunction "GND_JX3-71") (pintype "passive"))
      (node (ref "SOM1") (pin "JX3-72") (pinfunction "GND_JX3-72") (pintype "passive"))
      (node (ref "SOM1") (pin "JX3-77") (pinfunction "GND_JX3-77") (pintype "passive"))
      (node (ref "SOM1") (pin "JX3-78") (pinfunction "GND_JX3-78") (pintype "passive"))
      (node (ref "SOM1") (pin "JX3-83") (pinfunction "GND_JX3-83") (pintype "passive"))
      (node (ref "SOM1") (pin "JX3-84") (pinfunction "GND_JX3-84") (pintype "passive"))
      (node (ref "SOM1") (pin "JX3-89") (pinfunction "GND_JX3-89") (pintype "passive"))
      (node (ref "SOM1") (pin "JX3-90") (pinfunction "GND_JX3-90") (pintype "passive"))
      (node (ref "SOM1") (pin "JX3-95") (pinfunction "GND_JX3-95") (pintype "passive"))
      (node (ref "SOM1") (pin "JX3-96") (pinfunction "GND_JX3-96") (pintype "passive"))
      (node (ref "U27") (pin "4") (pinfunction "VSS_4") (pintype "passive"))
    )
    (net (code "175") (name "VCCO") (class "Default")
      (node (ref "C83") (pin "2") (pinfunction "2_2") (pintype "passive"))
      (node (ref "C87") (pin "2") (pinfunction "2_2") (pintype "passive"))
      (node (ref "C89") (pin "2") (pinfunction "2_2") (pintype "passive"))
      (node (ref "C90") (pin "2") (pinfunction "2_2") (pintype "passive"))
      (node (ref "SOM1") (pin "JX1-78") (pinfunction "VCCO_34_JX1-78") (pintype "passive"))
      (node (ref "SOM1") (pin "JX1-79") (pinfunction "VCCO_34_JX1-79") (pintype "passive"))
      (node (ref "SOM1") (pin "JX1-80") (pinfunction "VCCO_34_JX1-80") (pintype "passive"))
      (node (ref "SOM1") (pin "JX2-78") (pinfunction "VCCO_35_JX2-78") (pintype "passive"))
      (node (ref "SOM1") (pin "JX2-79") (pinfunction "VCCO_35_JX2-79") (pintype "passive"))
      (node (ref "SOM1") (pin "JX2-80") (pinfunction "VCCO_35_JX2-80") (pintype "passive"))
      (node (ref "SOM1") (pin "JX2-98") (pinfunction "VCCO_13_JX2-98") (pintype "passive"))
      (node (ref "SOM1") (pin "JX3-45") (pinfunction "VCCO_13_JX3-45") (pintype "passive"))
      (node (ref "SOM1") (pin "JX3-46") (pinfunction "VCCO_13_JX3-46") (pintype "passive"))
    )
    (net (code "176") (name "VIN_HDR") (class "Default")
      (node (ref "C104") (pin "2") (pinfunction "2_2") (pintype "passive"))
      (node (ref "C105") (pin "2") (pinfunction "2_2") (pintype "passive"))
      (node (ref "C106") (pin "2") (pinfunction "2_2") (pintype "passive"))
      (node (ref "SOM1") (pin "JX1-57") (pinfunction "VIN_HDR_JX1-57") (pintype "passive"))
      (node (ref "SOM1") (pin "JX1-58") (pinfunction "VIN_HDR_JX1-58") (pintype "passive"))
      (node (ref "SOM1") (pin "JX1-59") (pinfunction "VIN_HDR_JX1-59") (pintype "passive"))
      (node (ref "SOM1") (pin "JX1-60") (pinfunction "VIN_HDR_JX1-60") (pintype "passive"))
      (node (ref "SOM1") (pin "JX2-12") (pinfunction "VIN_HDR_JX2-12") (pintype "passive"))
      (node (ref "SOM1") (pin "JX2-57") (pinfunction "VIN_HDR_JX2-57") (pintype "passive"))
      (node (ref "SOM1") (pin "JX2-58") (pinfunction "VIN_HDR_JX2-58") (pintype "passive"))
      (node (ref "SOM1") (pin "JX2-59") (pinfunction "VIN_HDR_JX2-59") (pintype "passive"))
      (node (ref "SOM1") (pin "JX2-60") (pinfunction "VIN_HDR_JX2-60") (pintype "passive"))
    )
    (net (code "177") (name "unconnected-(SOM1A-BANK13_LVDS_2_N-PadJX1-93)") (class "Default")
      (node (ref "SOM1") (pin "JX1-93") (pinfunction "BANK13_LVDS_2_N_JX1-93") (pintype "passive+no_connect"))
    )
    (net (code "178") (name "unconnected-(SOM1A-BANK13_LVDS_2_P-PadJX1-91)") (class "Default")
      (node (ref "SOM1") (pin "JX1-91") (pinfunction "BANK13_LVDS_2_P_JX1-91") (pintype "passive+no_connect"))
    )
    (net (code "179") (name "unconnected-(SOM1A-FPGA_VBATT-PadJX1-7)") (class "Default")
      (node (ref "SOM1") (pin "JX1-7") (pinfunction "FPGA_VBATT_JX1-7") (pintype "passive"))
    )
    (net (code "180") (name "unconnected-(SOM1A-PWR_ENABLE-PadJX1-5)") (class "Default")
      (node (ref "SOM1") (pin "JX1-5") (pinfunction "PWR_ENABLE_JX1-5") (pintype "passive"))
    )
    (net (code "181") (name "unconnected-(SOM1B-INIT#-PadJX2-9)") (class "Default")
      (node (ref "SOM1") (pin "JX2-9") (pinfunction "INIT#_JX2-9") (pintype "passive"))
    )
    (net (code "182") (name "unconnected-(SOM1B-JX2_LVDS_6_N-PadJX2-37)") (class "Default")
      (node (ref "SOM1") (pin "JX2-37") (pinfunction "JX2_LVDS_6_N_JX2-37") (pintype "passive+no_connect"))
    )
    (net (code "183") (name "unconnected-(SOM1B-JX2_LVDS_10_N-PadJX2-49)") (class "Default")
      (node (ref "SOM1") (pin "JX2-49") (pinfunction "JX2_LVDS_10_N_JX2-49") (pintype "passive+no_connect"))
    )
    (net (code "184") (name "unconnected-(SOM1B-JX2_LVDS_10_P-PadJX2-47)") (class "Default")
      (node (ref "SOM1") (pin "JX2-47") (pinfunction "JX2_LVDS_10_P_JX2-47") (pintype "passive+no_connect"))
    )
    (net (code "185") (name "unconnected-(SOM1B-JX2_LVDS_12_N-PadJX2-55)") (class "Default")
      (node (ref "SOM1") (pin "JX2-55") (pinfunction "JX2_LVDS_12_N_JX2-55") (pintype "passive+no_connect"))
    )
    (net (code "186") (name "unconnected-(SOM1B-JX2_LVDS_12_P-PadJX2-53)") (class "Default")
      (node (ref "SOM1") (pin "JX2-53") (pinfunction "JX2_LVDS_12_P_JX2-53") (pintype "passive+no_connect"))
    )
    (net (code "187") (name "unconnected-(SOM1B-JX2_LVDS_14_N-PadJX2-63)") (class "Default")
      (node (ref "SOM1") (pin "JX2-63") (pinfunction "JX2_LVDS_14_N_JX2-63") (pintype "passive+no_connect"))
    )
    (net (code "188") (name "unconnected-(SOM1B-JX2_LVDS_14_P-PadJX2-61)") (class "Default")
      (node (ref "SOM1") (pin "JX2-61") (pinfunction "JX2_LVDS_14_P_JX2-61") (pintype "passive+no_connect"))
    )
    (net (code "189") (name "unconnected-(SOM1B-JX2_LVDS_18_P-PadJX2-73)") (class "Default")
      (node (ref "SOM1") (pin "JX2-73") (pinfunction "JX2_LVDS_18_P_JX2-73") (pintype "passive+no_connect"))
    )
    (net (code "190") (name "unconnected-(SOM1B-MIO0-PadJX2-7)") (class "Default")
      (node (ref "SOM1") (pin "JX2-7") (pinfunction "MIO0_JX2-7") (pintype "passive"))
    )
    (net (code "191") (name "unconnected-(SOM1B-MIO9-PadJX2-8)") (class "Default")
      (node (ref "SOM1") (pin "JX2-8") (pinfunction "MIO9_JX2-8") (pintype "passive"))
    )
    (net (code "192") (name "unconnected-(SOM1B-MIO10-PadJX2-1)") (class "Default")
      (node (ref "SOM1") (pin "JX2-1") (pinfunction "MIO10_JX2-1") (pintype "passive"))
    )
    (net (code "193") (name "unconnected-(SOM1B-MIO11-PadJX2-6)") (class "Default")
      (node (ref "SOM1") (pin "JX2-6") (pinfunction "MIO11_JX2-6") (pintype "passive"))
    )
    (net (code "194") (name "unconnected-(SOM1B-MIO12-PadJX2-5)") (class "Default")
      (node (ref "SOM1") (pin "JX2-5") (pinfunction "MIO12_JX2-5") (pintype "passive"))
    )
    (net (code "195") (name "unconnected-(SOM1B-MIO13-PadJX2-2)") (class "Default")
      (node (ref "SOM1") (pin "JX2-2") (pinfunction "MIO13_JX2-2") (pintype "passive"))
    )
    (net (code "196") (name "unconnected-(SOM1B-MIO14-PadJX2-3)") (class "Default")
      (node (ref "SOM1") (pin "JX2-3") (pinfunction "MIO14_JX2-3") (pintype "passive"))
    )
    (net (code "197") (name "unconnected-(SOM1B-MIO15-PadJX2-4)") (class "Default")
      (node (ref "SOM1") (pin "JX2-4") (pinfunction "MIO15_JX2-4") (pintype "passive"))
    )
    (net (code "198") (name "unconnected-(SOM1C-BANK13_LVDS_7_P-PadJX3-73)") (class "Default")
      (node (ref "SOM1") (pin "JX3-73") (pinfunction "BANK13_LVDS_7_P_JX3-73") (pintype "passive+no_connect"))
    )
    (net (code "199") (name "unconnected-(SOM1C-BANK13_LVDS_8_N-PadJX3-76)") (class "Default")
      (node (ref "SOM1") (pin "JX3-76") (pinfunction "BANK13_LVDS_8_N_JX3-76") (pintype "passive+no_connect"))
    )
    (net (code "200") (name "unconnected-(SOM1C-BANK13_LVDS_8_P-PadJX3-74)") (class "Default")
      (node (ref "SOM1") (pin "JX3-74") (pinfunction "BANK13_LVDS_8_P_JX3-74") (pintype "passive+no_connect"))
    )
    (net (code "201") (name "unconnected-(SOM1C-MGTAVCC-PadJX3-5)") (class "Default")
      (node (ref "SOM1") (pin "JX3-5") (pinfunction "MGTAVCC_JX3-5") (pintype "passive"))
    )
    (net (code "202") (name "unconnected-(SOM1C-MGTAVCC-PadJX3-7)") (class "Default")
      (node (ref "SOM1") (pin "JX3-7") (pinfunction "MGTAVCC_JX3-7") (pintype "passive"))
    )
    (net (code "203") (name "unconnected-(SOM1C-MGTAVCC-PadJX3-9)") (class "Default")
      (node (ref "SOM1") (pin "JX3-9") (pinfunction "MGTAVCC_JX3-9") (pintype "passive"))
    )
    (net (code "204") (name "unconnected-(SOM1C-MGTAVCC-PadJX3-11)") (class "Default")
      (node (ref "SOM1") (pin "JX3-11") (pinfunction "MGTAVCC_JX3-11") (pintype "passive"))
    )
    (net (code "205") (name "unconnected-(SOM1C-MGTAVTT-PadJX3-30)") (class "Default")
      (node (ref "SOM1") (pin "JX3-30") (pinfunction "MGTAVTT_JX3-30") (pintype "passive"))
    )
    (net (code "206") (name "unconnected-(SOM1C-MGTAVTT-PadJX3-32)") (class "Default")
      (node (ref "SOM1") (pin "JX3-32") (pinfunction "MGTAVTT_JX3-32") (pintype "passive"))
    )
    (net (code "207") (name "unconnected-(SOM1C-MGTREFCLK0_N-PadJX3-3)") (class "Default")
      (node (ref "SOM1") (pin "JX3-3") (pinfunction "MGTREFCLK0_N_JX3-3") (pintype "passive"))
    )
    (net (code "208") (name "unconnected-(SOM1C-MGTREFCLK0_P-PadJX3-1)") (class "Default")
      (node (ref "SOM1") (pin "JX3-1") (pinfunction "MGTREFCLK0_P_JX3-1") (pintype "passive"))
    )
    (net (code "209") (name "unconnected-(SOM1C-MGTREFCLK1_N-PadJX3-4)") (class "Default")
      (node (ref "SOM1") (pin "JX3-4") (pinfunction "MGTREFCLK1_N_JX3-4") (pintype "passive"))
    )
    (net (code "210") (name "unconnected-(SOM1C-MGTREFCLK1_P-PadJX3-2)") (class "Default")
      (node (ref "SOM1") (pin "JX3-2") (pinfunction "MGTREFCLK1_P_JX3-2") (pintype "passive"))
    )
    (net (code "211") (name "unconnected-(SOM1C-MGTRX0_N-PadJX3-10)") (class "Default")
      (node (ref "SOM1") (pin "JX3-10") (pinfunction "MGTRX0_N_JX3-10") (pintype "passive"))
    )
    (net (code "212") (name "unconnected-(SOM1C-MGTRX0_P-PadJX3-8)") (class "Default")
      (node (ref "SOM1") (pin "JX3-8") (pinfunction "MGTRX0_P_JX3-8") (pintype "passive"))
    )
    (net (code "213") (name "unconnected-(SOM1C-MGTRX1_N-PadJX3-16)") (class "Default")
      (node (ref "SOM1") (pin "JX3-16") (pinfunction "MGTRX1_N_JX3-16") (pintype "passive"))
    )
    (net (code "214") (name "unconnected-(SOM1C-MGTRX1_P-PadJX3-14)") (class "Default")
      (node (ref "SOM1") (pin "JX3-14") (pinfunction "MGTRX1_P_JX3-14") (pintype "passive"))
    )
    (net (code "215") (name "unconnected-(SOM1C-MGTRX2_N-PadJX3-22)") (class "Default")
      (node (ref "SOM1") (pin "JX3-22") (pinfunction "MGTRX2_N_JX3-22") (pintype "passive"))
    )
    (net (code "216") (name "unconnected-(SOM1C-MGTRX2_P-PadJX3-20)") (class "Default")
      (node (ref "SOM1") (pin "JX3-20") (pinfunction "MGTRX2_P_JX3-20") (pintype "passive"))
    )
    (net (code "217") (name "unconnected-(SOM1C-MGTRX3_N-PadJX3-28)") (class "Default")
      (node (ref "SOM1") (pin "JX3-28") (pinfunction "MGTRX3_N_JX3-28") (pintype "passive"))
    )
    (net (code "218") (name "unconnected-(SOM1C-MGTRX3_P-PadJX3-26)") (class "Default")
      (node (ref "SOM1") (pin "JX3-26") (pinfunction "MGTRX3_P_JX3-26") (pintype "passive"))
    )
    (net (code "219") (name "unconnected-(SOM1C-MGTTX0_N-PadJX3-15)") (class "Default")
      (node (ref "SOM1") (pin "JX3-15") (pinfunction "MGTTX0_N_JX3-15") (pintype "passive"))
    )
    (net (code "220") (name "unconnected-(SOM1C-MGTTX0_P-PadJX3-13)") (class "Default")
      (node (ref "SOM1") (pin "JX3-13") (pinfunction "MGTTX0_P_JX3-13") (pintype "passive"))
    )
    (net (code "221") (name "unconnected-(SOM1C-MGTTX1_N-PadJX3-21)") (class "Default")
      (node (ref "SOM1") (pin "JX3-21") (pinfunction "MGTTX1_N_JX3-21") (pintype "passive"))
    )
    (net (code "222") (name "unconnected-(SOM1C-MGTTX1_P-PadJX3-19)") (class "Default")
      (node (ref "SOM1") (pin "JX3-19") (pinfunction "MGTTX1_P_JX3-19") (pintype "passive"))
    )
    (net (code "223") (name "unconnected-(SOM1C-MGTTX2_N-PadJX3-27)") (class "Default")
      (node (ref "SOM1") (pin "JX3-27") (pinfunction "MGTTX2_N_JX3-27") (pintype "passive"))
    )
    (net (code "224") (name "unconnected-(SOM1C-MGTTX2_P-PadJX3-25)") (class "Default")
      (node (ref "SOM1") (pin "JX3-25") (pinfunction "MGTTX2_P_JX3-25") (pintype "passive"))
    )
    (net (code "225") (name "unconnected-(SOM1C-MGTTX3_N-PadJX3-33)") (class "Default")
      (node (ref "SOM1") (pin "JX3-33") (pinfunction "MGTTX3_N_JX3-33") (pintype "passive"))
    )
    (net (code "226") (name "unconnected-(SOM1C-MGTTX3_P-PadJX3-31)") (class "Default")
      (node (ref "SOM1") (pin "JX3-31") (pinfunction "MGTTX3_P_JX3-31") (pintype "passive"))
    )
    (net (code "227") (name "unconnected-(SOM1C-PS_MIO41-PadJX3-34)") (class "Default")
      (node (ref "SOM1") (pin "JX3-34") (pinfunction "PS_MIO41_JX3-34") (pintype "passive"))
    )
    (net (code "228") (name "unconnected-(SOM1C-PS_MIO43-PadJX3-36)") (class "Default")
      (node (ref "SOM1") (pin "JX3-36") (pinfunction "PS_MIO43_JX3-36") (pintype "passive"))
    )
    (net (code "229") (name "unconnected-(SOM1C-PS_MIO47-PadJX3-40)") (class "Default")
      (node (ref "SOM1") (pin "JX3-40") (pinfunction "PS_MIO47_JX3-40") (pintype "passive"))
    )
    (net (code "230") (name "unconnected-(SOM1C-PS_MIO48-PadJX3-42)") (class "Default")
      (node (ref "SOM1") (pin "JX3-42") (pinfunction "PS_MIO48_JX3-42") (pintype "passive"))
    )
    (net (code "231") (name "unconnected-(SOM1C-USB_ID-PadJX3-63)") (class "Default")
      (node (ref "SOM1") (pin "JX3-63") (pinfunction "USB_ID_JX3-63") (pintype "passive+no_connect"))
    )
    (net (code "232") (name "unconnected-(SOM1C-USB_OTG_CPEN-PadJX3-70)") (class "Default")
      (node (ref "SOM1") (pin "JX3-70") (pinfunction "USB_OTG_CPEN_JX3-70") (pintype "passive+no_connect"))
    )
    (net (code "233") (name "unconnected-(SOM1C-USB_OTG_N-PadJX3-69)") (class "Default")
      (node (ref "SOM1") (pin "JX3-69") (pinfunction "USB_OTG_N_JX3-69") (pintype "passive+no_connect"))
    )
    (net (code "234") (name "unconnected-(SOM1C-USB_OTG_P-PadJX3-67)") (class "Default")
      (node (ref "SOM1") (pin "JX3-67") (pinfunction "USB_OTG_P_JX3-67") (pintype "passive+no_connect"))
    )
    (net (code "235") (name "unconnected-(SOM1C-USB_VBUS_OTG-PadJX3-68)") (class "Default")
      (node (ref "SOM1") (pin "JX3-68") (pinfunction "USB_VBUS_OTG_JX3-68") (pintype "passive+no_connect"))
    )
  )
)
